# 06_SOM_USB_CARD.net
KiCad netlist of a schematic drawn in Altium Designer
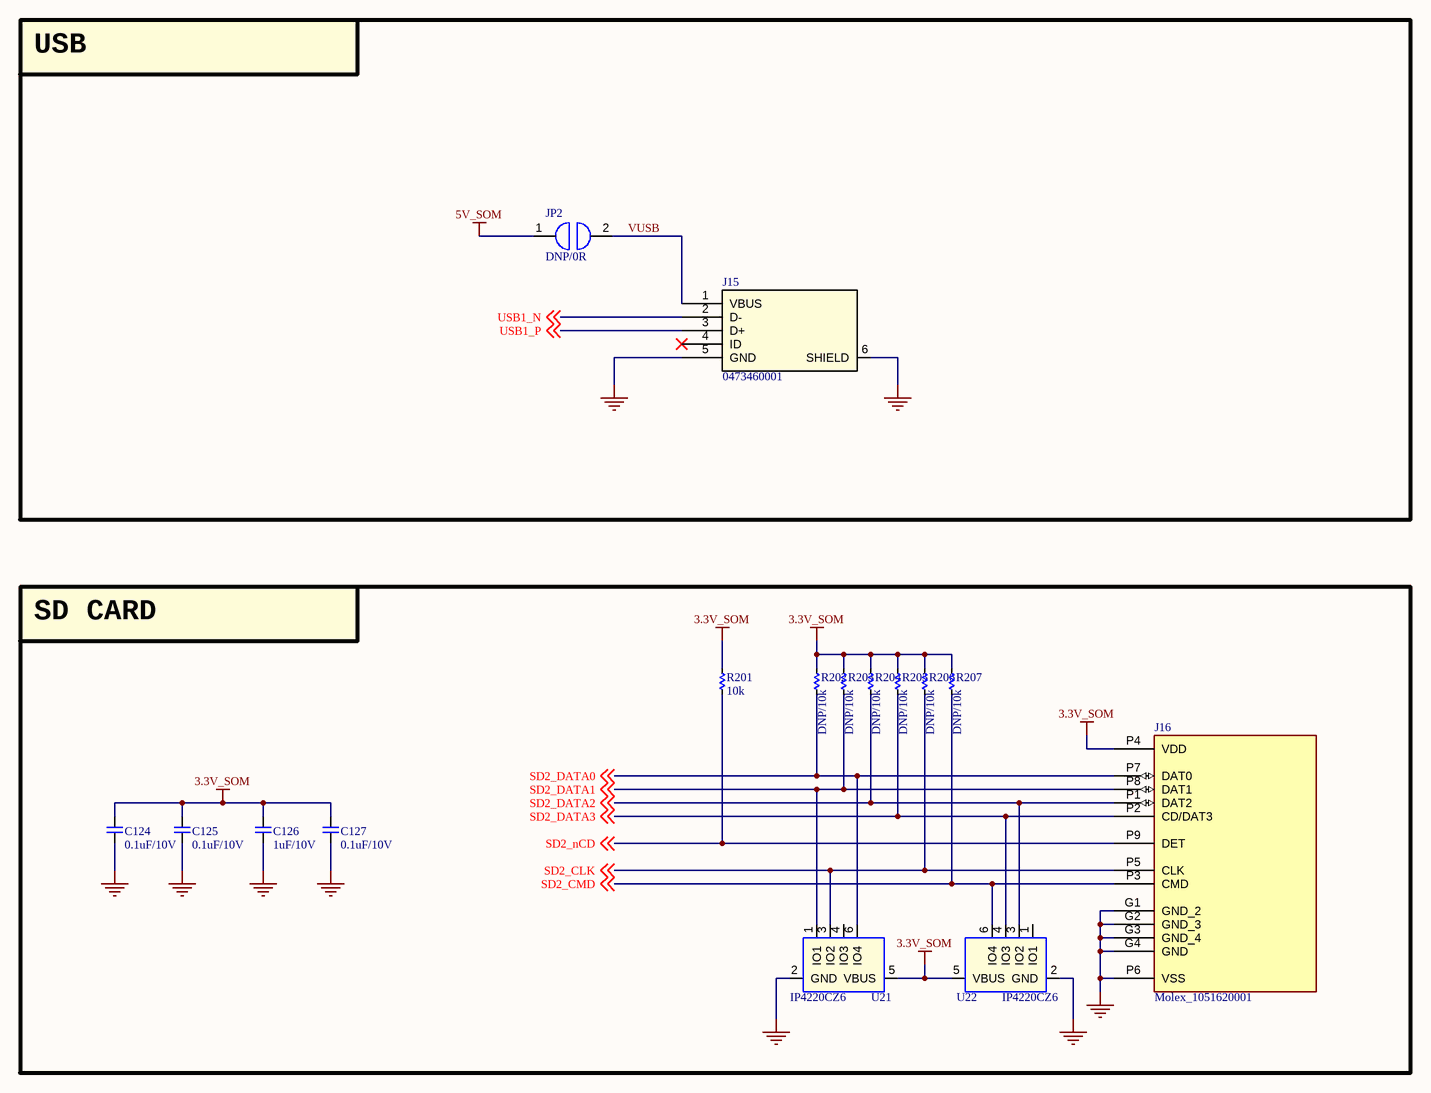
[diagram p0: 06_SOM_USB_CARD.SchDoc]

(export (version "E")
  (design (tool "Eeschema 10.0.6"))
  (components
    (comp (ref "C124")
      (value "0.1uF/10V")
      (footprint "CAP_C_1005X60")
      (description "CAP CHIP")
      (libsource (lib "LABLIB") (part "_CAP_C_2"))
    )
    (comp (ref "C125")
      (value "0.1uF/10V")
      (footprint "CAP_C_1005X60")
      (description "CAP CHIP")
      (libsource (lib "LABLIB") (part "_CAP_C_2"))
    )
    (comp (ref "C126")
      (value "1uF/10V")
      (footprint "CAP_C_1005X60")
      (description "CAP CHIP")
      (libsource (lib "LABLIB") (part "_CAP_C_2"))
    )
    (comp (ref "C127")
      (value "0.1uF/10V")
      (footprint "CAP_C_1005X60")
      (description "CAP CHIP")
      (libsource (lib "LABLIB") (part "_CAP_C_2"))
    )
    (comp (ref "J15")
      (value "0473460001")
      (footprint "47346-0001_MOL")
      (description "No Description Available")
      (libsource (lib "obc_ver2") (part "USB_micro"))
    )
    (comp (ref "J16")
      (value "Molex_1051620001")
      (footprint "Molex_1051620001")
      (description "9 (8 + 1) Position Card Connector Secure Digital - microSDâ„¢ Surface Mount, Right Angle Gold")
      (fields (field (name "MF") "Molex") (field (name "MP") "1051620001"))
      (libsource (lib "new_component") (part "Molex_1051620001"))
    )
    (comp (ref "JP2") (value "DNP/0R") (footprint "RES_C_1608X60") (libsource (lib "EXP_V1") (part "JUMPER")))
    (comp (ref "R201")
      (value "10k")
      (footprint "RES_C_1005X40")
      (description "RES")
      (libsource (lib "LABLIB") (part "_RES_B_2"))
    )
    (comp (ref "R202")
      (value "DNP/10k")
      (footprint "RES_C_1005X40")
      (description "RES")
      (libsource (lib "LABLIB") (part "_RES_B_2"))
    )
    (comp (ref "R203")
      (value "DNP/10k")
      (footprint "RES_C_1005X40")
      (description "RES")
      (libsource (lib "LABLIB") (part "_RES_B_2"))
    )
    (comp (ref "R204")
      (value "DNP/10k")
      (footprint "RES_C_1005X40")
      (description "RES")
      (libsource (lib "LABLIB") (part "_RES_B_2"))
    )
    (comp (ref "R205")
      (value "DNP/10k")
      (footprint "RES_C_1005X40")
      (description "RES")
      (libsource (lib "LABLIB") (part "_RES_B_2"))
    )
    (comp (ref "R206")
      (value "DNP/10k")
      (footprint "RES_C_1005X40")
      (description "RES")
      (libsource (lib "LABLIB") (part "_RES_B_2"))
    )
    (comp (ref "R207")
      (value "DNP/10k")
      (footprint "RES_C_1005X40")
      (description "RES")
      (libsource (lib "LABLIB") (part "_RES_B_2"))
    )
    (comp (ref "U21")
      (value "IP4220CZ6")
      (footprint "SOT95P280X145-6N")
      (libsource (lib "*") (part "IP4220CZ6_0"))
    )
    (comp (ref "U22")
      (value "IP4220CZ6")
      (footprint "SOT95P280X145-6N")
      (libsource (lib "") (part "IP4220CZ6_0_1"))
    )
  )
  (nets
    (net (code "1") (name "/VUSB") (class "Default")
      (node (ref "J15") (pin "1") (pinfunction "VBUS_1") (pintype "passive"))
      (node (ref "JP2") (pin "2") (pinfunction "2_2") (pintype "passive"))
    )
    (net (code "2") (name "3.3V_SOM") (class "Default")
      (node (ref "C124") (pin "2") (pinfunction "2_2") (pintype "passive"))
      (node (ref "C125") (pin "2") (pinfunction "2_2") (pintype "passive"))
      (node (ref "C126") (pin "2") (pinfunction "2_2") (pintype "passive"))
      (node (ref "C127") (pin "2") (pinfunction "2_2") (pintype "passive"))
      (node (ref "J16") (pin "P4") (pinfunction "VDD_P4") (pintype "power_in"))
      (node (ref "R201") (pin "2") (pinfunction "2_2") (pintype "passive"))
      (node (ref "R202") (pin "2") (pinfunction "2_2") (pintype "passive"))
      (node (ref "R203") (pin "2") (pinfunction "2_2") (pintype "passive"))
      (node (ref "R204") (pin "2") (pinfunction "2_2") (pintype "passive"))
      (node (ref "R205") (pin "2") (pinfunction "2_2") (pintype "passive"))
      (node (ref "R206") (pin "2") (pinfunction "2_2") (pintype "passive"))
      (node (ref "R207") (pin "2") (pinfunction "2_2") (pintype "passive"))
      (node (ref "U21") (pin "5") (pinfunction "VBUS_5") (pintype "passive"))
      (node (ref "U22") (pin "5") (pinfunction "VBUS_5") (pintype "passive"))
    )
    (net (code "3") (name "5V_SOM") (class "Default")
      (node (ref "JP2") (pin "1") (pinfunction "1_1") (pintype "passive"))
    )
    (net (code "4") (name "GND") (class "Default")
      (node (ref "C124") (pin "1") (pinfunction "1_1") (pintype "passive"))
      (node (ref "C125") (pin "1") (pinfunction "1_1") (pintype "passive"))
      (node (ref "C126") (pin "1") (pinfunction "1_1") (pintype "passive"))
      (node (ref "C127") (pin "1") (pinfunction "1_1") (pintype "passive"))
      (node (ref "J15") (pin "5") (pinfunction "GND_5") (pintype "power_in"))
      (node (ref "J15") (pin "6") (pinfunction "SHIELD_6") (pintype "passive"))
      (node (ref "J16") (pin "G1") (pinfunction "GND_2_G1") (pintype "passive"))
      (node (ref "J16") (pin "G2") (pinfunction "GND_3_G2") (pintype "passive"))
      (node (ref "J16") (pin "G3") (pinfunction "GND_4_G3") (pintype "passive"))
      (node (ref "J16") (pin "G4") (pinfunction "GND_G4") (pintype "passive"))
      (node (ref "J16") (pin "P6") (pinfunction "VSS_P6") (pintype "passive"))
      (node (ref "U21") (pin "2") (pinfunction "GND_2") (pintype "passive"))
      (node (ref "U22") (pin "2") (pinfunction "GND_2") (pintype "passive"))
    )
    (net (code "5") (name "SD2_CLK") (class "Default")
      (node (ref "J16") (pin "P5") (pinfunction "CLK_P5") (pintype "passive"))
      (node (ref "R206") (pin "1") (pinfunction "1_1") (pintype "passive"))
      (node (ref "U21") (pin "3") (pinfunction "IO2_3") (pintype "passive"))
    )
    (net (code "6") (name "SD2_CMD") (class "Default")
      (node (ref "J16") (pin "P3") (pinfunction "CMD_P3") (pintype "passive"))
      (node (ref "R207") (pin "1") (pinfunction "1_1") (pintype "passive"))
      (node (ref "U22") (pin "6") (pinfunction "IO4_6") (pintype "passive"))
    )
    (net (code "7") (name "SD2_DATA0") (class "Default")
      (node (ref "J16") (pin "P7") (pinfunction "DAT0_P7") (pintype "bidirectional"))
      (node (ref "R202") (pin "1") (pinfunction "1_1") (pintype "passive"))
      (node (ref "U21") (pin "6") (pinfunction "IO4_6") (pintype "passive"))
    )
    (net (code "8") (name "SD2_DATA1") (class "Default")
      (node (ref "J16") (pin "P8") (pinfunction "DAT1_P8") (pintype "bidirectional"))
      (node (ref "R203") (pin "1") (pinfunction "1_1") (pintype "passive"))
      (node (ref "U21") (pin "1") (pinfunction "IO1_1") (pintype "passive"))
    )
    (net (code "9") (name "SD2_DATA2") (class "Default")
      (node (ref "J16") (pin "P1") (pinfunction "DAT2_P1") (pintype "bidirectional"))
      (node (ref "R204") (pin "1") (pinfunction "1_1") (pintype "passive"))
      (node (ref "U22") (pin "3") (pinfunction "IO2_3") (pintype "passive"))
    )
    (net (code "10") (name "SD2_DATA3") (class "Default")
      (node (ref "J16") (pin "P2") (pinfunction "CD/DAT3_P2") (pintype "passive"))
      (node (ref "R205") (pin "1") (pinfunction "1_1") (pintype "passive"))
      (node (ref "U22") (pin "4") (pinfunction "IO3_4") (pintype "passive"))
    )
    (net (code "11") (name "SD2_nCD") (class "Default")
      (node (ref "J16") (pin "P9") (pinfunction "DET_P9") (pintype "passive"))
      (node (ref "R201") (pin "1") (pinfunction "1_1") (pintype "passive"))
    )
    (net (code "12") (name "USB1_N") (class "Default")
      (node (ref "J15") (pin "2") (pinfunction "D-_2") (pintype "passive"))
    )
    (net (code "13") (name "USB1_P") (class "Default")
      (node (ref "J15") (pin "3") (pinfunction "D+_3") (pintype "passive"))
    )
    (net (code "14") (name "unconnected-(J15-ID-Pad4)") (class "Default")
      (node (ref "J15") (pin "4") (pinfunction "ID_4") (pintype "passive+no_connect"))
    )
    (net (code "15") (name "unconnected-(U21-IO3-Pad4)") (class "Default")
      (node (ref "U21") (pin "4") (pinfunction "IO3_4") (pintype "passive"))
    )
    (net (code "16") (name "unconnected-(U22-IO1-Pad1)") (class "Default")
      (node (ref "U22") (pin "1") (pinfunction "IO1_1") (pintype "passive"))
    )
  )
)
